# li-ION_BATTERY_Charger.net
KiCad netlist of a schematic drawn in EAGLE
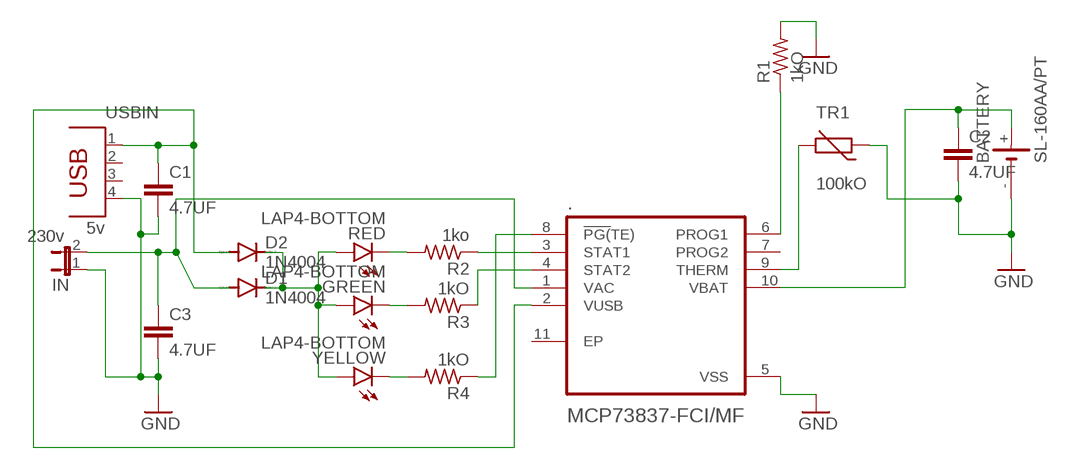
[diagram p0: schematic, sheet 1]

(export (version "E")
  (design (tool "Eeschema 10.0.6"))
  (components
    (comp (ref ".")
      (value "MCP73837-FCI/MF")
      (footprint "eagle-import:DFN300X300X100-11N")
      (fields (field (name "MF") "Microchip"))
      (libsource (lib "eagle-import") (part "MCP73837-FCI/MF"))
    )
    (comp (ref "BATTERY")
      (value "SL-160AA/PT")
      (footprint "eagle-import:SL-160AA_PT")
      (libsource (lib "eagle-import") (part "SL-160AA/PT"))
    )
    (comp (ref "C1")
      (value "4.7UF")
      (footprint "eagle-import:C5B2.5")
      (libsource (lib "eagle-import") (part "C5/2.5"))
    )
    (comp (ref "C2")
      (value "4.7UF")
      (footprint "eagle-import:C5B2.5")
      (libsource (lib "eagle-import") (part "C5/2.5"))
    )
    (comp (ref "C3")
      (value "4.7UF")
      (footprint "eagle-import:C5B2.5")
      (libsource (lib "eagle-import") (part "C5/2.5"))
    )
    (comp (ref "D1")
      (value "1N4004")
      (footprint "eagle-import:DO41-10")
      (libsource (lib "eagle-import") (part "1N4004"))
    )
    (comp (ref "D2")
      (value "1N4004")
      (footprint "eagle-import:DO41-10")
      (libsource (lib "eagle-import") (part "1N4004"))
    )
    (comp (ref "GREEN")
      (value "LAP4-BOTTOM")
      (footprint "eagle-import:P47F-BOTTOM")
      (libsource (lib "eagle-import") (part "P4-BOTTOMLA"))
    )
    (comp (ref "IN")
      (value "230v")
      (footprint "eagle-import:JP1")
      (libsource (lib "eagle-import") (part "JP1E"))
    )
    (comp (ref "R1")
      (value "1kO")
      (footprint "eagle-import:0309_12")
      (libsource (lib "eagle-import") (part "R-US_0309/12"))
    )
    (comp (ref "R2")
      (value "1ko")
      (footprint "eagle-import:0309_12")
      (libsource (lib "eagle-import") (part "R-US_0309/12"))
    )
    (comp (ref "R3")
      (value "1kO")
      (footprint "eagle-import:0309_12")
      (libsource (lib "eagle-import") (part "R-US_0309/12"))
    )
    (comp (ref "R4")
      (value "1kO")
      (footprint "eagle-import:0309_12")
      (libsource (lib "eagle-import") (part "R-US_0309/12"))
    )
    (comp (ref "RED")
      (value "LAP4-BOTTOM")
      (footprint "eagle-import:P47F-BOTTOM")
      (libsource (lib "eagle-import") (part "P4-BOTTOMLA"))
    )
    (comp (ref "TR1")
      (value "100kO")
      (footprint "eagle-import:R-7,5")
      (libsource (lib "eagle-import") (part "THERMISTOR_R-7,5"))
    )
    (comp (ref "USBIN")
      (value "5v")
      (footprint "eagle-import:PN87520")
      (libsource (lib "eagle-import") (part "PN87520"))
    )
    (comp (ref "YELLOW")
      (value "LAP4-BOTTOM")
      (footprint "eagle-import:P47F-BOTTOM")
      (libsource (lib "eagle-import") (part "P4-BOTTOMLA"))
    )
  )
  (nets
    (net (code "1") (name "GND") (class "Default")
      (node (ref ".") (pin "5") (pinfunction "VSS_5") (pintype "power_in"))
      (node (ref "BATTERY") (pin "-") (pinfunction "-_-") (pintype "passive"))
      (node (ref "C1") (pin "2") (pinfunction "2_2") (pintype "passive"))
      (node (ref "C2") (pin "2") (pinfunction "2_2") (pintype "passive"))
      (node (ref "C3") (pin "2") (pinfunction "2_2") (pintype "passive"))
      (node (ref "IN") (pin "1") (pinfunction "1_1") (pintype "passive"))
      (node (ref "R1") (pin "2") (pinfunction "2_2") (pintype "passive"))
      (node (ref "TR1") (pin "1") (pinfunction "1_1") (pintype "passive"))
      (node (ref "USBIN") (pin "4") (pinfunction "4_4") (pintype "passive"))
    )
    (net (code "2") (name "Net-(.-PROG1)") (class "Default")
      (node (ref ".") (pin "6") (pinfunction "PROG1_6") (pintype "output"))
      (node (ref "R1") (pin "1") (pinfunction "1_1") (pintype "passive"))
    )
    (net (code "3") (name "Net-(.-STAT1)") (class "Default")
      (node (ref ".") (pin "3") (pinfunction "STAT1_3") (pintype "input"))
      (node (ref "R2") (pin "1") (pinfunction "1_1") (pintype "passive"))
    )
    (net (code "4") (name "Net-(.-STAT2)") (class "Default")
      (node (ref ".") (pin "4") (pinfunction "STAT2_4") (pintype "input"))
      (node (ref "R3") (pin "1") (pinfunction "1_1") (pintype "passive"))
    )
    (net (code "5") (name "Net-(.-THERM)") (class "Default")
      (node (ref ".") (pin "9") (pinfunction "THERM_9") (pintype "output"))
      (node (ref "TR1") (pin "2") (pinfunction "2_2") (pintype "passive"))
    )
    (net (code "6") (name "Net-(.-VAC)") (class "Default")
      (node (ref ".") (pin "1") (pinfunction "VAC_1") (pintype "input"))
      (node (ref "C3") (pin "1") (pinfunction "1_1") (pintype "passive"))
      (node (ref "D1") (pin "A") (pinfunction "A_A") (pintype "passive"))
      (node (ref "IN") (pin "2") (pinfunction "2_2") (pintype "passive"))
    )
    (net (code "7") (name "Net-(.-VBAT)") (class "Default")
      (node (ref ".") (pin "10") (pinfunction "VBAT_10") (pintype "output"))
      (node (ref "BATTERY") (pin "+") (pinfunction "+_+") (pintype "passive"))
      (node (ref "C2") (pin "1") (pinfunction "1_1") (pintype "passive"))
    )
    (net (code "8") (name "Net-(.-VUSB)") (class "Default")
      (node (ref ".") (pin "2") (pinfunction "VUSB_2") (pintype "input"))
      (node (ref "C1") (pin "1") (pinfunction "1_1") (pintype "passive"))
      (node (ref "D2") (pin "A") (pinfunction "A_A") (pintype "passive"))
      (node (ref "USBIN") (pin "1") (pinfunction "1_1") (pintype "passive"))
    )
    (net (code "9") (name "Net-(.-~{PG(}TE))") (class "Default")
      (node (ref ".") (pin "8") (pinfunction "~{PG(}TE)_8") (pintype "input"))
      (node (ref "R4") (pin "1") (pinfunction "1_1") (pintype "passive"))
    )
    (net (code "10") (name "Net-(D1-PadC)") (class "Default")
      (node (ref "D1") (pin "C") (pinfunction "C_C") (pintype "passive"))
      (node (ref "D2") (pin "C") (pinfunction "C_C") (pintype "passive"))
      (node (ref "GREEN") (pin "A") (pinfunction "A_A") (pintype "passive"))
      (node (ref "RED") (pin "A") (pinfunction "A_A") (pintype "passive"))
      (node (ref "YELLOW") (pin "A") (pinfunction "A_A") (pintype "passive"))
    )
    (net (code "11") (name "Net-(GREEN-PadC)") (class "Default")
      (node (ref "GREEN") (pin "C") (pinfunction "C_C") (pintype "passive"))
      (node (ref "R3") (pin "2") (pinfunction "2_2") (pintype "passive"))
    )
    (net (code "12") (name "Net-(R2-Pad2)") (class "Default")
      (node (ref "R2") (pin "2") (pinfunction "2_2") (pintype "passive"))
      (node (ref "RED") (pin "C") (pinfunction "C_C") (pintype "passive"))
    )
    (net (code "13") (name "Net-(R4-Pad2)") (class "Default")
      (node (ref "R4") (pin "2") (pinfunction "2_2") (pintype "passive"))
      (node (ref "YELLOW") (pin "C") (pinfunction "C_C") (pintype "passive"))
    )
    (net (code "14") (name "unconnected-(.-EP-Pad11)") (class "Default")
      (node (ref ".") (pin "11") (pinfunction "EP_11") (pintype "bidirectional"))
    )
    (net (code "15") (name "unconnected-(.-PROG2-Pad7)") (class "Default")
      (node (ref ".") (pin "7") (pinfunction "PROG2_7") (pintype "output"))
    )
    (net (code "16") (name "unconnected-(BATTERY---Pad-@1)") (class "Default")
      (node (ref "BATTERY") (pin "-@1") (pinfunction "-_-@1") (pintype "passive"))
    )
    (net (code "17") (name "unconnected-(USBIN-Pad2)") (class "Default")
      (node (ref "USBIN") (pin "2") (pinfunction "2_2") (pintype "passive"))
    )
    (net (code "18") (name "unconnected-(USBIN-Pad3)") (class "Default")
      (node (ref "USBIN") (pin "3") (pinfunction "3_3") (pintype "passive"))
    )
  )
)
